# Sheet4.net
KiCad netlist of a schematic drawn in Altium Designer
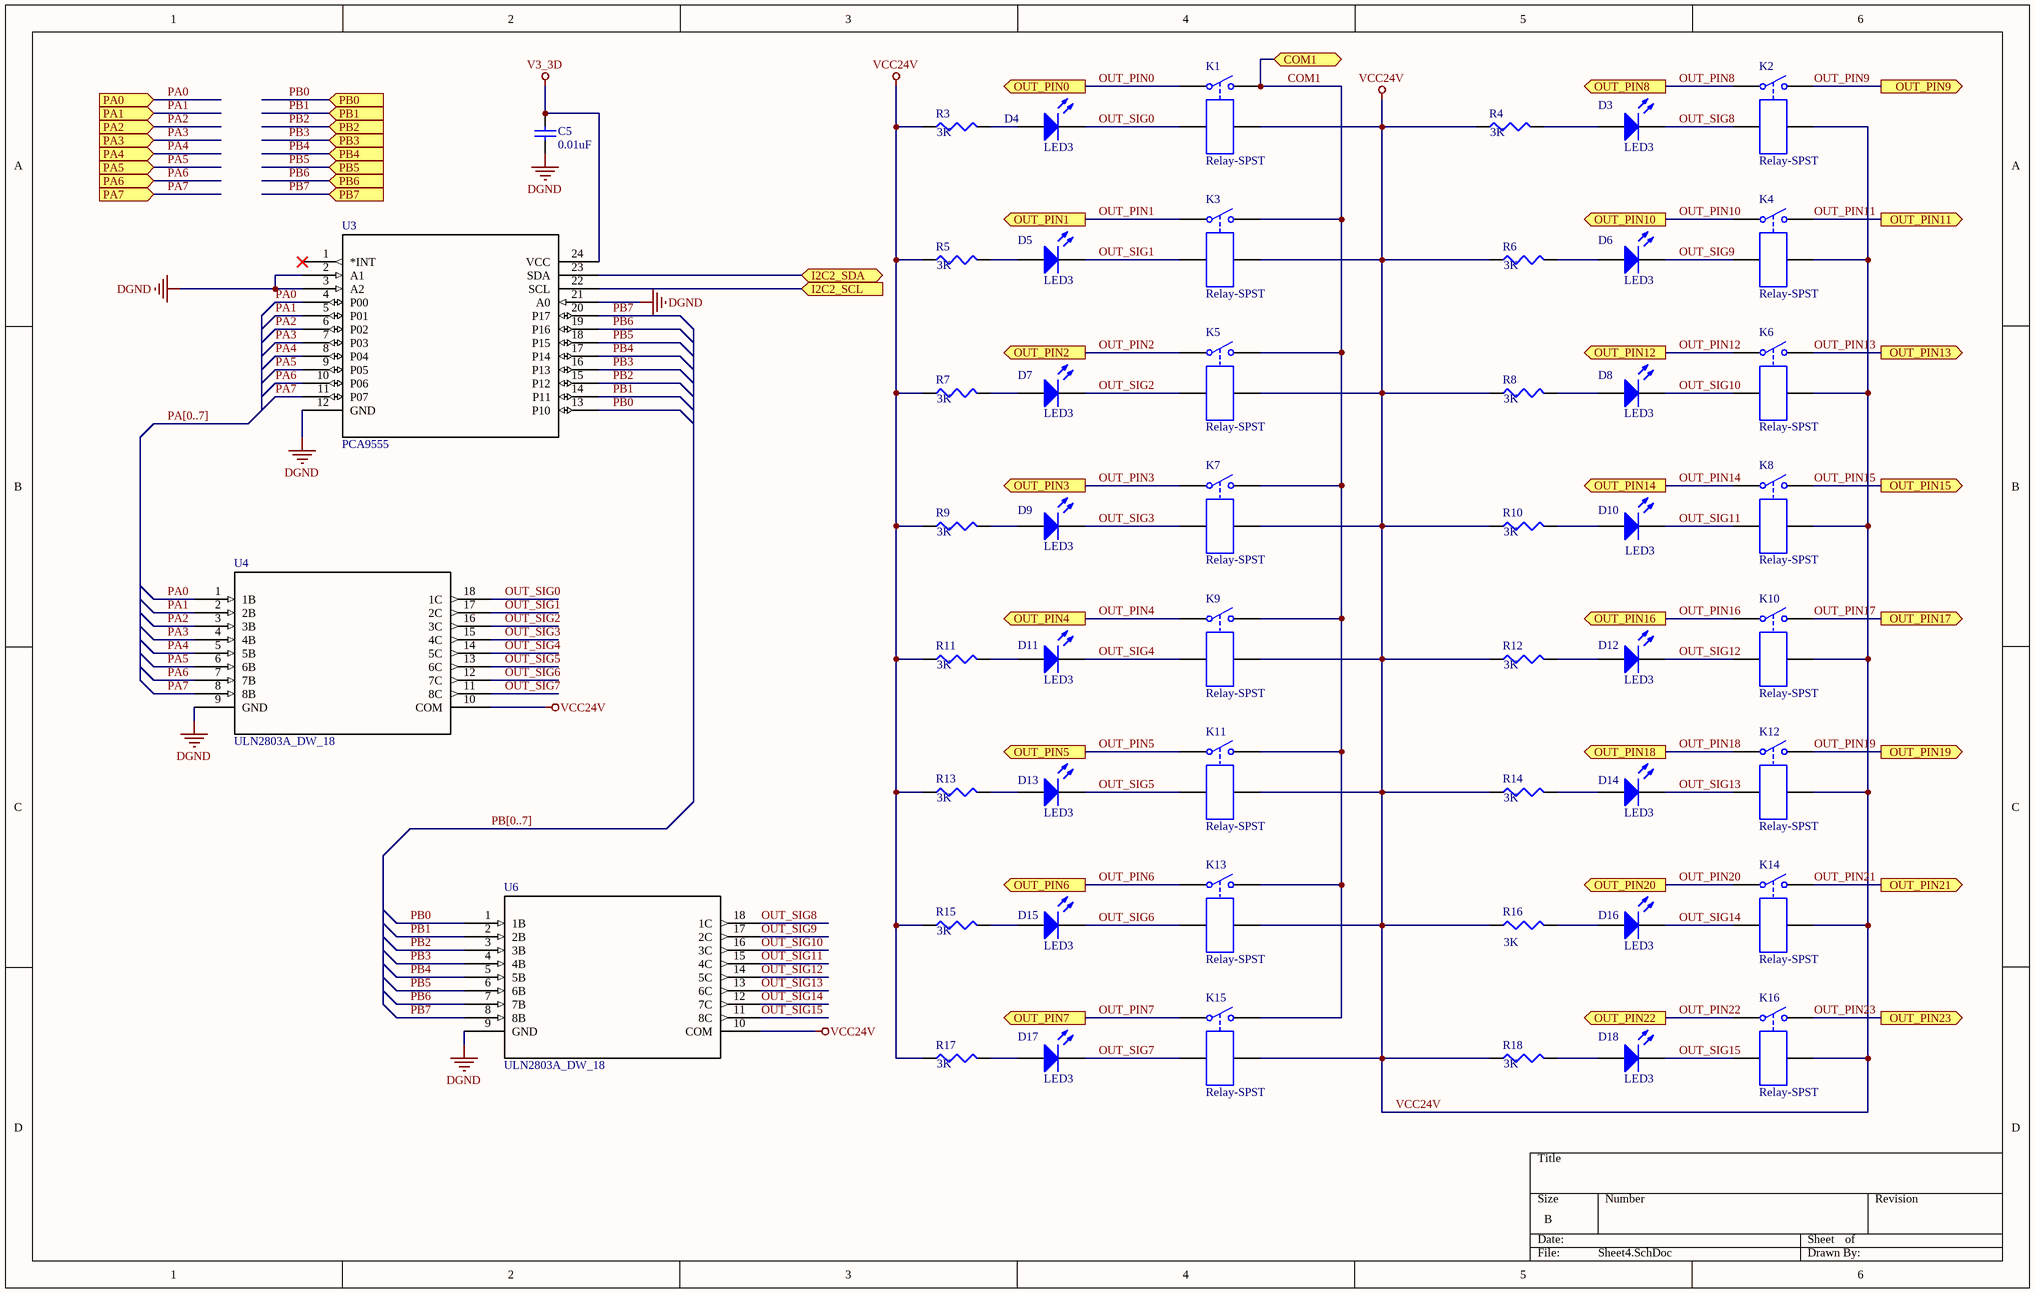
[diagram p0: Sheet4.SchDoc]

(export (version "E")
  (design (tool "Eeschema 10.0.6"))
  (components
    (comp (ref "C5")
      (value "0.01uF")
      (footprint "0805_cap")
      (description "Capacitor")
      (fields (field (name "PUBLISHER") "Altium Limited"))
      (libsource (lib "Miscellaneous Devices") (part "Cap"))
    )
    (comp (ref "D3")
      (value "LED3")
      (footprint "0805LED")
      (description "Typical BLUE SiC LED")
      (fields (field (name "PUBLISHER") "Altium Limited"))
      (libsource (lib "Miscellaneous Devices") (part "LED3"))
    )
    (comp (ref "D4")
      (value "LED3")
      (footprint "0805LED")
      (description "Typical BLUE SiC LED")
      (fields (field (name "PUBLISHER") "Altium Limited"))
      (libsource (lib "Miscellaneous Devices") (part "LED3"))
    )
    (comp (ref "D5")
      (value "LED3")
      (footprint "0805LED")
      (description "Typical BLUE SiC LED")
      (fields (field (name "PUBLISHER") "Altium Limited"))
      (libsource (lib "Miscellaneous Devices") (part "LED3"))
    )
    (comp (ref "D6")
      (value "LED3")
      (footprint "0805LED")
      (description "Typical BLUE SiC LED")
      (fields (field (name "PUBLISHER") "Altium Limited"))
      (libsource (lib "Miscellaneous Devices") (part "LED3"))
    )
    (comp (ref "D7")
      (value "LED3")
      (footprint "0805LED")
      (description "Typical BLUE SiC LED")
      (fields (field (name "PUBLISHER") "Altium Limited"))
      (libsource (lib "Miscellaneous Devices") (part "LED3"))
    )
    (comp (ref "D8")
      (value "LED3")
      (footprint "0805LED")
      (description "Typical BLUE SiC LED")
      (fields (field (name "PUBLISHER") "Altium Limited"))
      (libsource (lib "Miscellaneous Devices") (part "LED3"))
    )
    (comp (ref "D9")
      (value "LED3")
      (footprint "0805LED")
      (description "Typical BLUE SiC LED")
      (fields (field (name "PUBLISHER") "Altium Limited"))
      (libsource (lib "Miscellaneous Devices") (part "LED3"))
    )
    (comp (ref "D10")
      (value "LED3")
      (footprint "0805LED")
      (description "Typical BLUE SiC LED")
      (fields (field (name "PUBLISHER") "Altium Limited"))
      (libsource (lib "Miscellaneous Devices") (part "LED3"))
    )
    (comp (ref "D11")
      (value "LED3")
      (footprint "0805LED")
      (description "Typical BLUE SiC LED")
      (fields (field (name "PUBLISHER") "Altium Limited"))
      (libsource (lib "Miscellaneous Devices") (part "LED3"))
    )
    (comp (ref "D12")
      (value "LED3")
      (footprint "0805LED")
      (description "Typical BLUE SiC LED")
      (fields (field (name "PUBLISHER") "Altium Limited"))
      (libsource (lib "Miscellaneous Devices") (part "LED3"))
    )
    (comp (ref "D13")
      (value "LED3")
      (footprint "0805LED")
      (description "Typical BLUE SiC LED")
      (fields (field (name "PUBLISHER") "Altium Limited"))
      (libsource (lib "Miscellaneous Devices") (part "LED3"))
    )
    (comp (ref "D14")
      (value "LED3")
      (footprint "0805LED")
      (description "Typical BLUE SiC LED")
      (fields (field (name "PUBLISHER") "Altium Limited"))
      (libsource (lib "Miscellaneous Devices") (part "LED3"))
    )
    (comp (ref "D15")
      (value "LED3")
      (footprint "0805LED")
      (description "Typical BLUE SiC LED")
      (fields (field (name "PUBLISHER") "Altium Limited"))
      (libsource (lib "Miscellaneous Devices") (part "LED3"))
    )
    (comp (ref "D16")
      (value "LED3")
      (footprint "0805LED")
      (description "Typical BLUE SiC LED")
      (fields (field (name "PUBLISHER") "Altium Limited"))
      (libsource (lib "Miscellaneous Devices") (part "LED3"))
    )
    (comp (ref "D17")
      (value "LED3")
      (footprint "0805LED")
      (description "Typical BLUE SiC LED")
      (fields (field (name "PUBLISHER") "Altium Limited"))
      (libsource (lib "Miscellaneous Devices") (part "LED3"))
    )
    (comp (ref "D18")
      (value "LED3")
      (footprint "0805LED")
      (description "Typical BLUE SiC LED")
      (fields (field (name "PUBLISHER") "Altium Limited"))
      (libsource (lib "Miscellaneous Devices") (part "LED3"))
    )
    (comp (ref "K1")
      (value "Relay-SPST")
      (footprint "PA1a-24v")
      (description "Single-Pole Single-Throw Relay")
      (fields (field (name "PUBLISHER") "Altium Limited"))
      (libsource (lib "Miscellaneous Devices") (part "Relay-SPST"))
    )
    (comp (ref "K2")
      (value "Relay-SPST")
      (footprint "PA1a-24v")
      (description "Single-Pole Single-Throw Relay")
      (fields (field (name "PUBLISHER") "Altium Limited"))
      (libsource (lib "Miscellaneous Devices") (part "Relay-SPST"))
    )
    (comp (ref "K3")
      (value "Relay-SPST")
      (footprint "PA1a-24v")
      (description "Single-Pole Single-Throw Relay")
      (fields (field (name "PUBLISHER") "Altium Limited"))
      (libsource (lib "Miscellaneous Devices") (part "Relay-SPST"))
    )
    (comp (ref "K4")
      (value "Relay-SPST")
      (footprint "PA1a-24v")
      (description "Single-Pole Single-Throw Relay")
      (fields (field (name "PUBLISHER") "Altium Limited"))
      (libsource (lib "Miscellaneous Devices") (part "Relay-SPST"))
    )
    (comp (ref "K5")
      (value "Relay-SPST")
      (footprint "PA1a-24v")
      (description "Single-Pole Single-Throw Relay")
      (fields (field (name "PUBLISHER") "Altium Limited"))
      (libsource (lib "Miscellaneous Devices") (part "Relay-SPST"))
    )
    (comp (ref "K6")
      (value "Relay-SPST")
      (footprint "PA1a-24v")
      (description "Single-Pole Single-Throw Relay")
      (fields (field (name "PUBLISHER") "Altium Limited"))
      (libsource (lib "Miscellaneous Devices") (part "Relay-SPST"))
    )
    (comp (ref "K7")
      (value "Relay-SPST")
      (footprint "PA1a-24v")
      (description "Single-Pole Single-Throw Relay")
      (fields (field (name "PUBLISHER") "Altium Limited"))
      (libsource (lib "Miscellaneous Devices") (part "Relay-SPST"))
    )
    (comp (ref "K8")
      (value "Relay-SPST")
      (footprint "PA1a-24v")
      (description "Single-Pole Single-Throw Relay")
      (fields (field (name "PUBLISHER") "Altium Limited"))
      (libsource (lib "Miscellaneous Devices") (part "Relay-SPST"))
    )
    (comp (ref "K9")
      (value "Relay-SPST")
      (footprint "PA1a-24v")
      (description "Single-Pole Single-Throw Relay")
      (fields (field (name "PUBLISHER") "Altium Limited"))
      (libsource (lib "Miscellaneous Devices") (part "Relay-SPST"))
    )
    (comp (ref "K10")
      (value "Relay-SPST")
      (footprint "PA1a-24v")
      (description "Single-Pole Single-Throw Relay")
      (fields (field (name "PUBLISHER") "Altium Limited"))
      (libsource (lib "Miscellaneous Devices") (part "Relay-SPST"))
    )
    (comp (ref "K11")
      (value "Relay-SPST")
      (footprint "PA1a-24v")
      (description "Single-Pole Single-Throw Relay")
      (fields (field (name "PUBLISHER") "Altium Limited"))
      (libsource (lib "Miscellaneous Devices") (part "Relay-SPST"))
    )
    (comp (ref "K12")
      (value "Relay-SPST")
      (footprint "PA1a-24v")
      (description "Single-Pole Single-Throw Relay")
      (fields (field (name "PUBLISHER") "Altium Limited"))
      (libsource (lib "Miscellaneous Devices") (part "Relay-SPST"))
    )
    (comp (ref "K13")
      (value "Relay-SPST")
      (footprint "PA1a-24v")
      (description "Single-Pole Single-Throw Relay")
      (fields (field (name "PUBLISHER") "Altium Limited"))
      (libsource (lib "Miscellaneous Devices") (part "Relay-SPST"))
    )
    (comp (ref "K14")
      (value "Relay-SPST")
      (footprint "PA1a-24v")
      (description "Single-Pole Single-Throw Relay")
      (fields (field (name "PUBLISHER") "Altium Limited"))
      (libsource (lib "Miscellaneous Devices") (part "Relay-SPST"))
    )
    (comp (ref "K15")
      (value "Relay-SPST")
      (footprint "PA1a-24v")
      (description "Single-Pole Single-Throw Relay")
      (fields (field (name "PUBLISHER") "Altium Limited"))
      (libsource (lib "Miscellaneous Devices") (part "Relay-SPST"))
    )
    (comp (ref "K16")
      (value "Relay-SPST")
      (footprint "PA1a-24v")
      (description "Single-Pole Single-Throw Relay")
      (fields (field (name "PUBLISHER") "Altium Limited"))
      (libsource (lib "Miscellaneous Devices") (part "Relay-SPST"))
    )
    (comp (ref "R3")
      (value "3K")
      (footprint "0805")
      (description "Resistor")
      (fields (field (name "PUBLISHER") "Altium Limited"))
      (libsource (lib "Miscellaneous Devices") (part "Res3"))
    )
    (comp (ref "R4")
      (value "3K")
      (footprint "0805")
      (description "Resistor")
      (fields (field (name "PUBLISHER") "Altium Limited"))
      (libsource (lib "Miscellaneous Devices") (part "Res3"))
    )
    (comp (ref "R5")
      (value "3K")
      (footprint "0805")
      (description "Resistor")
      (fields (field (name "PUBLISHER") "Altium Limited"))
      (libsource (lib "Miscellaneous Devices") (part "Res3"))
    )
    (comp (ref "R6")
      (value "3K")
      (footprint "0805")
      (description "Resistor")
      (fields (field (name "PUBLISHER") "Altium Limited"))
      (libsource (lib "Miscellaneous Devices") (part "Res3"))
    )
    (comp (ref "R7")
      (value "3K")
      (footprint "0805")
      (description "Resistor")
      (fields (field (name "PUBLISHER") "Altium Limited"))
      (libsource (lib "Miscellaneous Devices") (part "Res3"))
    )
    (comp (ref "R8")
      (value "3K")
      (footprint "0805")
      (description "Resistor")
      (fields (field (name "PUBLISHER") "Altium Limited"))
      (libsource (lib "Miscellaneous Devices") (part "Res3"))
    )
    (comp (ref "R9")
      (value "3K")
      (footprint "0805")
      (description "Resistor")
      (fields (field (name "PUBLISHER") "Altium Limited"))
      (libsource (lib "Miscellaneous Devices") (part "Res3"))
    )
    (comp (ref "R10")
      (value "3K")
      (footprint "0805")
      (description "Resistor")
      (fields (field (name "PUBLISHER") "Altium Limited"))
      (libsource (lib "Miscellaneous Devices") (part "Res3"))
    )
    (comp (ref "R11")
      (value "3K")
      (footprint "0805")
      (description "Resistor")
      (fields (field (name "PUBLISHER") "Altium Limited"))
      (libsource (lib "Miscellaneous Devices") (part "Res3"))
    )
    (comp (ref "R12")
      (value "3K")
      (footprint "0805")
      (description "Resistor")
      (fields (field (name "PUBLISHER") "Altium Limited"))
      (libsource (lib "Miscellaneous Devices") (part "Res3"))
    )
    (comp (ref "R13")
      (value "3K")
      (footprint "0805")
      (description "Resistor")
      (fields (field (name "PUBLISHER") "Altium Limited"))
      (libsource (lib "Miscellaneous Devices") (part "Res3"))
    )
    (comp (ref "R14")
      (value "3K")
      (footprint "0805")
      (description "Resistor")
      (fields (field (name "PUBLISHER") "Altium Limited"))
      (libsource (lib "Miscellaneous Devices") (part "Res3"))
    )
    (comp (ref "R15")
      (value "3K")
      (footprint "0805")
      (description "Resistor")
      (fields (field (name "PUBLISHER") "Altium Limited"))
      (libsource (lib "Miscellaneous Devices") (part "Res3"))
    )
    (comp (ref "R16")
      (value "3K")
      (footprint "0805")
      (description "Resistor")
      (fields (field (name "PUBLISHER") "Altium Limited"))
      (libsource (lib "Miscellaneous Devices") (part "Res3"))
    )
    (comp (ref "R17")
      (value "3K")
      (footprint "0805")
      (description "Resistor")
      (fields (field (name "PUBLISHER") "Altium Limited"))
      (libsource (lib "Miscellaneous Devices") (part "Res3"))
    )
    (comp (ref "R18")
      (value "3K")
      (footprint "0805")
      (description "Resistor")
      (fields (field (name "PUBLISHER") "Altium Limited"))
      (libsource (lib "Miscellaneous Devices") (part "Res3"))
    )
    (comp (ref "U3")
      (value "PCA9555")
      (footprint "PW24")
      (description "Imported")
      (fields
        (field (name "MANUFACTURER") "Texas Instruments")
        (field (name "GENERIC_PART_NUMBER") "PCF8575")
      )
      (libsource (lib "dolphi_ecs") (part "PCF8575_PW_24"))
    )
    (comp (ref "U4")
      (value "ULN2803A_DW_18")
      (footprint "DW18")
      (description "Imported")
      (fields
        (field (name "MANUFACTURER") "Texas Instruments")
        (field (name "GENERIC_PART_NUMBER") "ULN2803A")
      )
      (libsource (lib "dolphi_ecs") (part "ULN2803A_DW_18"))
    )
    (comp (ref "U6")
      (value "ULN2803A_DW_18")
      (footprint "DW18")
      (description "Imported")
      (fields
        (field (name "MANUFACTURER") "Texas Instruments")
        (field (name "GENERIC_PART_NUMBER") "ULN2803A")
      )
      (libsource (lib "dolphi_ecs") (part "ULN2803A_DW_18"))
    )
  )
  (nets
    (net (code "1") (name "/COM1") (class "Default")
      (node (ref "K1") (pin "2") (pinfunction "2_2") (pintype "passive"))
      (node (ref "K11") (pin "2") (pinfunction "2_2") (pintype "passive"))
      (node (ref "K13") (pin "2") (pinfunction "2_2") (pintype "passive"))
      (node (ref "K15") (pin "2") (pinfunction "2_2") (pintype "passive"))
      (node (ref "K3") (pin "2") (pinfunction "2_2") (pintype "passive"))
      (node (ref "K5") (pin "2") (pinfunction "2_2") (pintype "passive"))
      (node (ref "K7") (pin "2") (pinfunction "2_2") (pintype "passive"))
      (node (ref "K9") (pin "2") (pinfunction "2_2") (pintype "passive"))
    )
    (net (code "2") (name "/I2C2_SCL") (class "Default")
      (node (ref "U3") (pin "22") (pinfunction "SCL_22") (pintype "passive"))
    )
    (net (code "3") (name "/I2C2_SDA") (class "Default")
      (node (ref "U3") (pin "23") (pinfunction "SDA_23") (pintype "passive"))
    )
    (net (code "4") (name "/OUT_PIN0") (class "Default")
      (node (ref "K1") (pin "1") (pinfunction "1_1") (pintype "passive"))
    )
    (net (code "5") (name "/OUT_PIN1") (class "Default")
      (node (ref "K3") (pin "1") (pinfunction "1_1") (pintype "passive"))
    )
    (net (code "6") (name "/OUT_PIN2") (class "Default")
      (node (ref "K5") (pin "1") (pinfunction "1_1") (pintype "passive"))
    )
    (net (code "7") (name "/OUT_PIN3") (class "Default")
      (node (ref "K7") (pin "1") (pinfunction "1_1") (pintype "passive"))
    )
    (net (code "8") (name "/OUT_PIN4") (class "Default")
      (node (ref "K9") (pin "1") (pinfunction "1_1") (pintype "passive"))
    )
    (net (code "9") (name "/OUT_PIN5") (class "Default")
      (node (ref "K11") (pin "1") (pinfunction "1_1") (pintype "passive"))
    )
    (net (code "10") (name "/OUT_PIN6") (class "Default")
      (node (ref "K13") (pin "1") (pinfunction "1_1") (pintype "passive"))
    )
    (net (code "11") (name "/OUT_PIN7") (class "Default")
      (node (ref "K15") (pin "1") (pinfunction "1_1") (pintype "passive"))
    )
    (net (code "12") (name "/OUT_PIN8") (class "Default")
      (node (ref "K2") (pin "1") (pinfunction "1_1") (pintype "passive"))
    )
    (net (code "13") (name "/OUT_PIN9") (class "Default")
      (node (ref "K2") (pin "2") (pinfunction "2_2") (pintype "passive"))
    )
    (net (code "14") (name "/OUT_PIN10") (class "Default")
      (node (ref "K4") (pin "1") (pinfunction "1_1") (pintype "passive"))
    )
    (net (code "15") (name "/OUT_PIN11") (class "Default")
      (node (ref "K4") (pin "2") (pinfunction "2_2") (pintype "passive"))
    )
    (net (code "16") (name "/OUT_PIN12") (class "Default")
      (node (ref "K6") (pin "1") (pinfunction "1_1") (pintype "passive"))
    )
    (net (code "17") (name "/OUT_PIN13") (class "Default")
      (node (ref "K6") (pin "2") (pinfunction "2_2") (pintype "passive"))
    )
    (net (code "18") (name "/OUT_PIN14") (class "Default")
      (node (ref "K8") (pin "1") (pinfunction "1_1") (pintype "passive"))
    )
    (net (code "19") (name "/OUT_PIN15") (class "Default")
      (node (ref "K8") (pin "2") (pinfunction "2_2") (pintype "passive"))
    )
    (net (code "20") (name "/OUT_PIN16") (class "Default")
      (node (ref "K10") (pin "1") (pinfunction "1_1") (pintype "passive"))
    )
    (net (code "21") (name "/OUT_PIN17") (class "Default")
      (node (ref "K10") (pin "2") (pinfunction "2_2") (pintype "passive"))
    )
    (net (code "22") (name "/OUT_PIN18") (class "Default")
      (node (ref "K12") (pin "1") (pinfunction "1_1") (pintype "passive"))
    )
    (net (code "23") (name "/OUT_PIN19") (class "Default")
      (node (ref "K12") (pin "2") (pinfunction "2_2") (pintype "passive"))
    )
    (net (code "24") (name "/OUT_PIN20") (class "Default")
      (node (ref "K14") (pin "1") (pinfunction "1_1") (pintype "passive"))
    )
    (net (code "25") (name "/OUT_PIN21") (class "Default")
      (node (ref "K14") (pin "2") (pinfunction "2_2") (pintype "passive"))
    )
    (net (code "26") (name "/OUT_PIN22") (class "Default")
      (node (ref "K16") (pin "1") (pinfunction "1_1") (pintype "passive"))
    )
    (net (code "27") (name "/OUT_PIN23") (class "Default")
      (node (ref "K16") (pin "2") (pinfunction "2_2") (pintype "passive"))
    )
    (net (code "28") (name "/OUT_SIG0") (class "Default")
      (node (ref "D4") (pin "2") (pinfunction "K_2") (pintype "passive"))
      (node (ref "K1") (pin "3") (pinfunction "3_3") (pintype "passive"))
      (node (ref "U4") (pin "18") (pinfunction "1C_18") (pintype "output"))
    )
    (net (code "29") (name "/OUT_SIG1") (class "Default")
      (node (ref "D5") (pin "2") (pinfunction "K_2") (pintype "passive"))
      (node (ref "K3") (pin "3") (pinfunction "3_3") (pintype "passive"))
      (node (ref "U4") (pin "17") (pinfunction "2C_17") (pintype "output"))
    )
    (net (code "30") (name "/OUT_SIG2") (class "Default")
      (node (ref "D7") (pin "2") (pinfunction "K_2") (pintype "passive"))
      (node (ref "K5") (pin "3") (pinfunction "3_3") (pintype "passive"))
      (node (ref "U4") (pin "16") (pinfunction "3C_16") (pintype "output"))
    )
    (net (code "31") (name "/OUT_SIG3") (class "Default")
      (node (ref "D9") (pin "2") (pinfunction "K_2") (pintype "passive"))
      (node (ref "K7") (pin "3") (pinfunction "3_3") (pintype "passive"))
      (node (ref "U4") (pin "15") (pinfunction "4C_15") (pintype "output"))
    )
    (net (code "32") (name "/OUT_SIG4") (class "Default")
      (node (ref "D11") (pin "2") (pinfunction "K_2") (pintype "passive"))
      (node (ref "K9") (pin "3") (pinfunction "3_3") (pintype "passive"))
      (node (ref "U4") (pin "14") (pinfunction "5C_14") (pintype "output"))
    )
    (net (code "33") (name "/OUT_SIG5") (class "Default")
      (node (ref "D13") (pin "2") (pinfunction "K_2") (pintype "passive"))
      (node (ref "K11") (pin "3") (pinfunction "3_3") (pintype "passive"))
      (node (ref "U4") (pin "13") (pinfunction "6C_13") (pintype "output"))
    )
    (net (code "34") (name "/OUT_SIG6") (class "Default")
      (node (ref "D15") (pin "2") (pinfunction "K_2") (pintype "passive"))
      (node (ref "K13") (pin "3") (pinfunction "3_3") (pintype "passive"))
      (node (ref "U4") (pin "12") (pinfunction "7C_12") (pintype "output"))
    )
    (net (code "35") (name "/OUT_SIG7") (class "Default")
      (node (ref "D17") (pin "2") (pinfunction "K_2") (pintype "passive"))
      (node (ref "K15") (pin "3") (pinfunction "3_3") (pintype "passive"))
      (node (ref "U4") (pin "11") (pinfunction "8C_11") (pintype "output"))
    )
    (net (code "36") (name "/OUT_SIG8") (class "Default")
      (node (ref "D3") (pin "2") (pinfunction "K_2") (pintype "passive"))
      (node (ref "K2") (pin "3") (pinfunction "3_3") (pintype "passive"))
      (node (ref "U6") (pin "18") (pinfunction "1C_18") (pintype "output"))
    )
    (net (code "37") (name "/OUT_SIG9") (class "Default")
      (node (ref "D6") (pin "2") (pinfunction "K_2") (pintype "passive"))
      (node (ref "K4") (pin "3") (pinfunction "3_3") (pintype "passive"))
      (node (ref "U6") (pin "17") (pinfunction "2C_17") (pintype "output"))
    )
    (net (code "38") (name "/OUT_SIG10") (class "Default")
      (node (ref "D8") (pin "2") (pinfunction "K_2") (pintype "passive"))
      (node (ref "K6") (pin "3") (pinfunction "3_3") (pintype "passive"))
      (node (ref "U6") (pin "16") (pinfunction "3C_16") (pintype "output"))
    )
    (net (code "39") (name "/OUT_SIG11") (class "Default")
      (node (ref "D10") (pin "2") (pinfunction "K_2") (pintype "passive"))
      (node (ref "K8") (pin "3") (pinfunction "3_3") (pintype "passive"))
      (node (ref "U6") (pin "15") (pinfunction "4C_15") (pintype "output"))
    )
    (net (code "40") (name "/OUT_SIG12") (class "Default")
      (node (ref "D12") (pin "2") (pinfunction "K_2") (pintype "passive"))
      (node (ref "K10") (pin "3") (pinfunction "3_3") (pintype "passive"))
      (node (ref "U6") (pin "14") (pinfunction "5C_14") (pintype "output"))
    )
    (net (code "41") (name "/OUT_SIG13") (class "Default")
      (node (ref "D14") (pin "2") (pinfunction "K_2") (pintype "passive"))
      (node (ref "K12") (pin "3") (pinfunction "3_3") (pintype "passive"))
      (node (ref "U6") (pin "13") (pinfunction "6C_13") (pintype "output"))
    )
    (net (code "42") (name "/OUT_SIG14") (class "Default")
      (node (ref "D16") (pin "2") (pinfunction "K_2") (pintype "passive"))
      (node (ref "K14") (pin "3") (pinfunction "3_3") (pintype "passive"))
      (node (ref "U6") (pin "12") (pinfunction "7C_12") (pintype "output"))
    )
    (net (code "43") (name "/OUT_SIG15") (class "Default")
      (node (ref "D18") (pin "2") (pinfunction "K_2") (pintype "passive"))
      (node (ref "K16") (pin "3") (pinfunction "3_3") (pintype "passive"))
      (node (ref "U6") (pin "11") (pinfunction "8C_11") (pintype "output"))
    )
    (net (code "44") (name "/PA0") (class "Default")
      (node (ref "U3") (pin "4") (pinfunction "P00_4") (pintype "bidirectional"))
      (node (ref "U4") (pin "1") (pinfunction "1B_1") (pintype "input"))
    )
    (net (code "45") (name "/PA1") (class "Default")
      (node (ref "U3") (pin "5") (pinfunction "P01_5") (pintype "bidirectional"))
      (node (ref "U4") (pin "2") (pinfunction "2B_2") (pintype "input"))
    )
    (net (code "46") (name "/PA2") (class "Default")
      (node (ref "U3") (pin "6") (pinfunction "P02_6") (pintype "bidirectional"))
      (node (ref "U4") (pin "3") (pinfunction "3B_3") (pintype "input"))
    )
    (net (code "47") (name "/PA3") (class "Default")
      (node (ref "U3") (pin "7") (pinfunction "P03_7") (pintype "bidirectional"))
      (node (ref "U4") (pin "4") (pinfunction "4B_4") (pintype "input"))
    )
    (net (code "48") (name "/PA4") (class "Default")
      (node (ref "U3") (pin "8") (pinfunction "P04_8") (pintype "bidirectional"))
      (node (ref "U4") (pin "5") (pinfunction "5B_5") (pintype "input"))
    )
    (net (code "49") (name "/PA5") (class "Default")
      (node (ref "U3") (pin "9") (pinfunction "P05_9") (pintype "bidirectional"))
      (node (ref "U4") (pin "6") (pinfunction "6B_6") (pintype "input"))
    )
    (net (code "50") (name "/PA6") (class "Default")
      (node (ref "U3") (pin "10") (pinfunction "P06_10") (pintype "bidirectional"))
      (node (ref "U4") (pin "7") (pinfunction "7B_7") (pintype "input"))
    )
    (net (code "51") (name "/PA7") (class "Default")
      (node (ref "U3") (pin "11") (pinfunction "P07_11") (pintype "bidirectional"))
      (node (ref "U4") (pin "8") (pinfunction "8B_8") (pintype "input"))
    )
    (net (code "53") (name "/PB0") (class "Default")
      (node (ref "U3") (pin "13") (pinfunction "P10_13") (pintype "bidirectional"))
      (node (ref "U6") (pin "1") (pinfunction "1B_1") (pintype "input"))
    )
    (net (code "54") (name "/PB1") (class "Default")
      (node (ref "U3") (pin "14") (pinfunction "P11_14") (pintype "bidirectional"))
      (node (ref "U6") (pin "2") (pinfunction "2B_2") (pintype "input"))
    )
    (net (code "55") (name "/PB2") (class "Default")
      (node (ref "U3") (pin "15") (pinfunction "P12_15") (pintype "bidirectional"))
      (node (ref "U6") (pin "3") (pinfunction "3B_3") (pintype "input"))
    )
    (net (code "56") (name "/PB3") (class "Default")
      (node (ref "U3") (pin "16") (pinfunction "P13_16") (pintype "bidirectional"))
      (node (ref "U6") (pin "4") (pinfunction "4B_4") (pintype "input"))
    )
    (net (code "57") (name "/PB4") (class "Default")
      (node (ref "U3") (pin "17") (pinfunction "P14_17") (pintype "bidirectional"))
      (node (ref "U6") (pin "5") (pinfunction "5B_5") (pintype "input"))
    )
    (net (code "58") (name "/PB5") (class "Default")
      (node (ref "U3") (pin "18") (pinfunction "P15_18") (pintype "bidirectional"))
      (node (ref "U6") (pin "6") (pinfunction "6B_6") (pintype "input"))
    )
    (net (code "59") (name "/PB6") (class "Default")
      (node (ref "U3") (pin "19") (pinfunction "P16_19") (pintype "bidirectional"))
      (node (ref "U6") (pin "7") (pinfunction "7B_7") (pintype "input"))
    )
    (net (code "60") (name "/PB7") (class "Default")
      (node (ref "U3") (pin "20") (pinfunction "P17_20") (pintype "bidirectional"))
      (node (ref "U6") (pin "8") (pinfunction "8B_8") (pintype "input"))
    )
    (net (code "62") (name "DGND") (class "Default")
      (node (ref "C5") (pin "1") (pinfunction "1_1") (pintype "passive"))
      (node (ref "U3") (pin "12") (pinfunction "GND_12") (pintype "power_in"))
      (node (ref "U3") (pin "2") (pinfunction "A1_2") (pintype "input"))
      (node (ref "U3") (pin "21") (pinfunction "A0_21") (pintype "input"))
      (node (ref "U3") (pin "3") (pinfunction "A2_3") (pintype "input"))
      (node (ref "U4") (pin "9") (pinfunction "GND_9") (pintype "power_in"))
      (node (ref "U6") (pin "9") (pinfunction "GND_9") (pintype "power_in"))
    )
    (net (code "63") (name "Net-(D3-A)") (class "Default")
      (node (ref "D3") (pin "1") (pinfunction "A_1") (pintype "passive"))
      (node (ref "R4") (pin "2") (pinfunction "2_2") (pintype "passive"))
    )
    (net (code "64") (name "Net-(D4-A)") (class "Default")
      (node (ref "D4") (pin "1") (pinfunction "A_1") (pintype "passive"))
      (node (ref "R3") (pin "2") (pinfunction "2_2") (pintype "passive"))
    )
    (net (code "65") (name "Net-(D5-A)") (class "Default")
      (node (ref "D5") (pin "1") (pinfunction "A_1") (pintype "passive"))
      (node (ref "R5") (pin "2") (pinfunction "2_2") (pintype "passive"))
    )
    (net (code "66") (name "Net-(D6-A)") (class "Default")
      (node (ref "D6") (pin "1") (pinfunction "A_1") (pintype "passive"))
      (node (ref "R6") (pin "2") (pinfunction "2_2") (pintype "passive"))
    )
    (net (code "67") (name "Net-(D7-A)") (class "Default")
      (node (ref "D7") (pin "1") (pinfunction "A_1") (pintype "passive"))
      (node (ref "R7") (pin "2") (pinfunction "2_2") (pintype "passive"))
    )
    (net (code "68") (name "Net-(D8-A)") (class "Default")
      (node (ref "D8") (pin "1") (pinfunction "A_1") (pintype "passive"))
      (node (ref "R8") (pin "2") (pinfunction "2_2") (pintype "passive"))
    )
    (net (code "69") (name "Net-(D9-A)") (class "Default")
      (node (ref "D9") (pin "1") (pinfunction "A_1") (pintype "passive"))
      (node (ref "R9") (pin "2") (pinfunction "2_2") (pintype "passive"))
    )
    (net (code "70") (name "Net-(D10-A)") (class "Default")
      (node (ref "D10") (pin "1") (pinfunction "A_1") (pintype "passive"))
      (node (ref "R10") (pin "2") (pinfunction "2_2") (pintype "passive"))
    )
    (net (code "71") (name "Net-(D11-A)") (class "Default")
      (node (ref "D11") (pin "1") (pinfunction "A_1") (pintype "passive"))
      (node (ref "R11") (pin "2") (pinfunction "2_2") (pintype "passive"))
    )
    (net (code "72") (name "Net-(D12-A)") (class "Default")
      (node (ref "D12") (pin "1") (pinfunction "A_1") (pintype "passive"))
      (node (ref "R12") (pin "2") (pinfunction "2_2") (pintype "passive"))
    )
    (net (code "73") (name "Net-(D13-A)") (class "Default")
      (node (ref "D13") (pin "1") (pinfunction "A_1") (pintype "passive"))
      (node (ref "R13") (pin "2") (pinfunction "2_2") (pintype "passive"))
    )
    (net (code "74") (name "Net-(D14-A)") (class "Default")
      (node (ref "D14") (pin "1") (pinfunction "A_1") (pintype "passive"))
      (node (ref "R14") (pin "2") (pinfunction "2_2") (pintype "passive"))
    )
    (net (code "75") (name "Net-(D15-A)") (class "Default")
      (node (ref "D15") (pin "1") (pinfunction "A_1") (pintype "passive"))
      (node (ref "R15") (pin "2") (pinfunction "2_2") (pintype "passive"))
    )
    (net (code "76") (name "Net-(D16-A)") (class "Default")
      (node (ref "D16") (pin "1") (pinfunction "A_1") (pintype "passive"))
      (node (ref "R16") (pin "2") (pinfunction "2_2") (pintype "passive"))
    )
    (net (code "77") (name "Net-(D17-A)") (class "Default")
      (node (ref "D17") (pin "1") (pinfunction "A_1") (pintype "passive"))
      (node (ref "R17") (pin "2") (pinfunction "2_2") (pintype "passive"))
    )
    (net (code "78") (name "Net-(D18-A)") (class "Default")
      (node (ref "D18") (pin "1") (pinfunction "A_1") (pintype "passive"))
      (node (ref "R18") (pin "2") (pinfunction "2_2") (pintype "passive"))
    )
    (net (code "79") (name "V3_3D") (class "Default")
      (node (ref "C5") (pin "2") (pinfunction "2_2") (pintype "passive"))
      (node (ref "U3") (pin "24") (pinfunction "VCC_24") (pintype "power_in"))
    )
    (net (code "80") (name "VCC24V") (class "Default")
      (node (ref "K1") (pin "4") (pinfunction "4_4") (pintype "passive"))
      (node (ref "K10") (pin "4") (pinfunction "4_4") (pintype "passive"))
      (node (ref "K11") (pin "4") (pinfunction "4_4") (pintype "passive"))
      (node (ref "K12") (pin "4") (pinfunction "4_4") (pintype "passive"))
      (node (ref "K13") (pin "4") (pinfunction "4_4") (pintype "passive"))
      (node (ref "K14") (pin "4") (pinfunction "4_4") (pintype "passive"))
      (node (ref "K15") (pin "4") (pinfunction "4_4") (pintype "passive"))
      (node (ref "K16") (pin "4") (pinfunction "4_4") (pintype "passive"))
      (node (ref "K2") (pin "4") (pinfunction "4_4") (pintype "passive"))
      (node (ref "K3") (pin "4") (pinfunction "4_4") (pintype "passive"))
      (node (ref "K4") (pin "4") (pinfunction "4_4") (pintype "passive"))
      (node (ref "K5") (pin "4") (pinfunction "4_4") (pintype "passive"))
      (node (ref "K6") (pin "4") (pinfunction "4_4") (pintype "passive"))
      (node (ref "K7") (pin "4") (pinfunction "4_4") (pintype "passive"))
      (node (ref "K8") (pin "4") (pinfunction "4_4") (pintype "passive"))
      (node (ref "K9") (pin "4") (pinfunction "4_4") (pintype "passive"))
      (node (ref "R10") (pin "1") (pinfunction "1_1") (pintype "passive"))
      (node (ref "R11") (pin "1") (pinfunction "1_1") (pintype "passive"))
      (node (ref "R12") (pin "1") (pinfunction "1_1") (pintype "passive"))
      (node (ref "R13") (pin "1") (pinfunction "1_1") (pintype "passive"))
      (node (ref "R14") (pin "1") (pinfunction "1_1") (pintype "passive"))
      (node (ref "R15") (pin "1") (pinfunction "1_1") (pintype "passive"))
      (node (ref "R16") (pin "1") (pinfunction "1_1") (pintype "passive"))
      (node (ref "R17") (pin "1") (pinfunction "1_1") (pintype "passive"))
      (node (ref "R18") (pin "1") (pinfunction "1_1") (pintype "passive"))
      (node (ref "R3") (pin "1") (pinfunction "1_1") (pintype "passive"))
      (node (ref "R4") (pin "1") (pinfunction "1_1") (pintype "passive"))
      (node (ref "R5") (pin "1") (pinfunction "1_1") (pintype "passive"))
      (node (ref "R6") (pin "1") (pinfunction "1_1") (pintype "passive"))
      (node (ref "R7") (pin "1") (pinfunction "1_1") (pintype "passive"))
      (node (ref "R8") (pin "1") (pinfunction "1_1") (pintype "passive"))
      (node (ref "R9") (pin "1") (pinfunction "1_1") (pintype "passive"))
      (node (ref "U4") (pin "10") (pinfunction "COM_10") (pintype "passive"))
      (node (ref "U6") (pin "10") (pinfunction "COM_10") (pintype "passive"))
    )
    (net (code "81") (name "unconnected-(U3-*INT-Pad1)") (class "Default")
      (node (ref "U3") (pin "1") (pinfunction "*INT_1") (pintype "output+no_connect"))
    )
  )
)
